# B250D.net
KiCad netlist of a schematic drawn in EAGLE
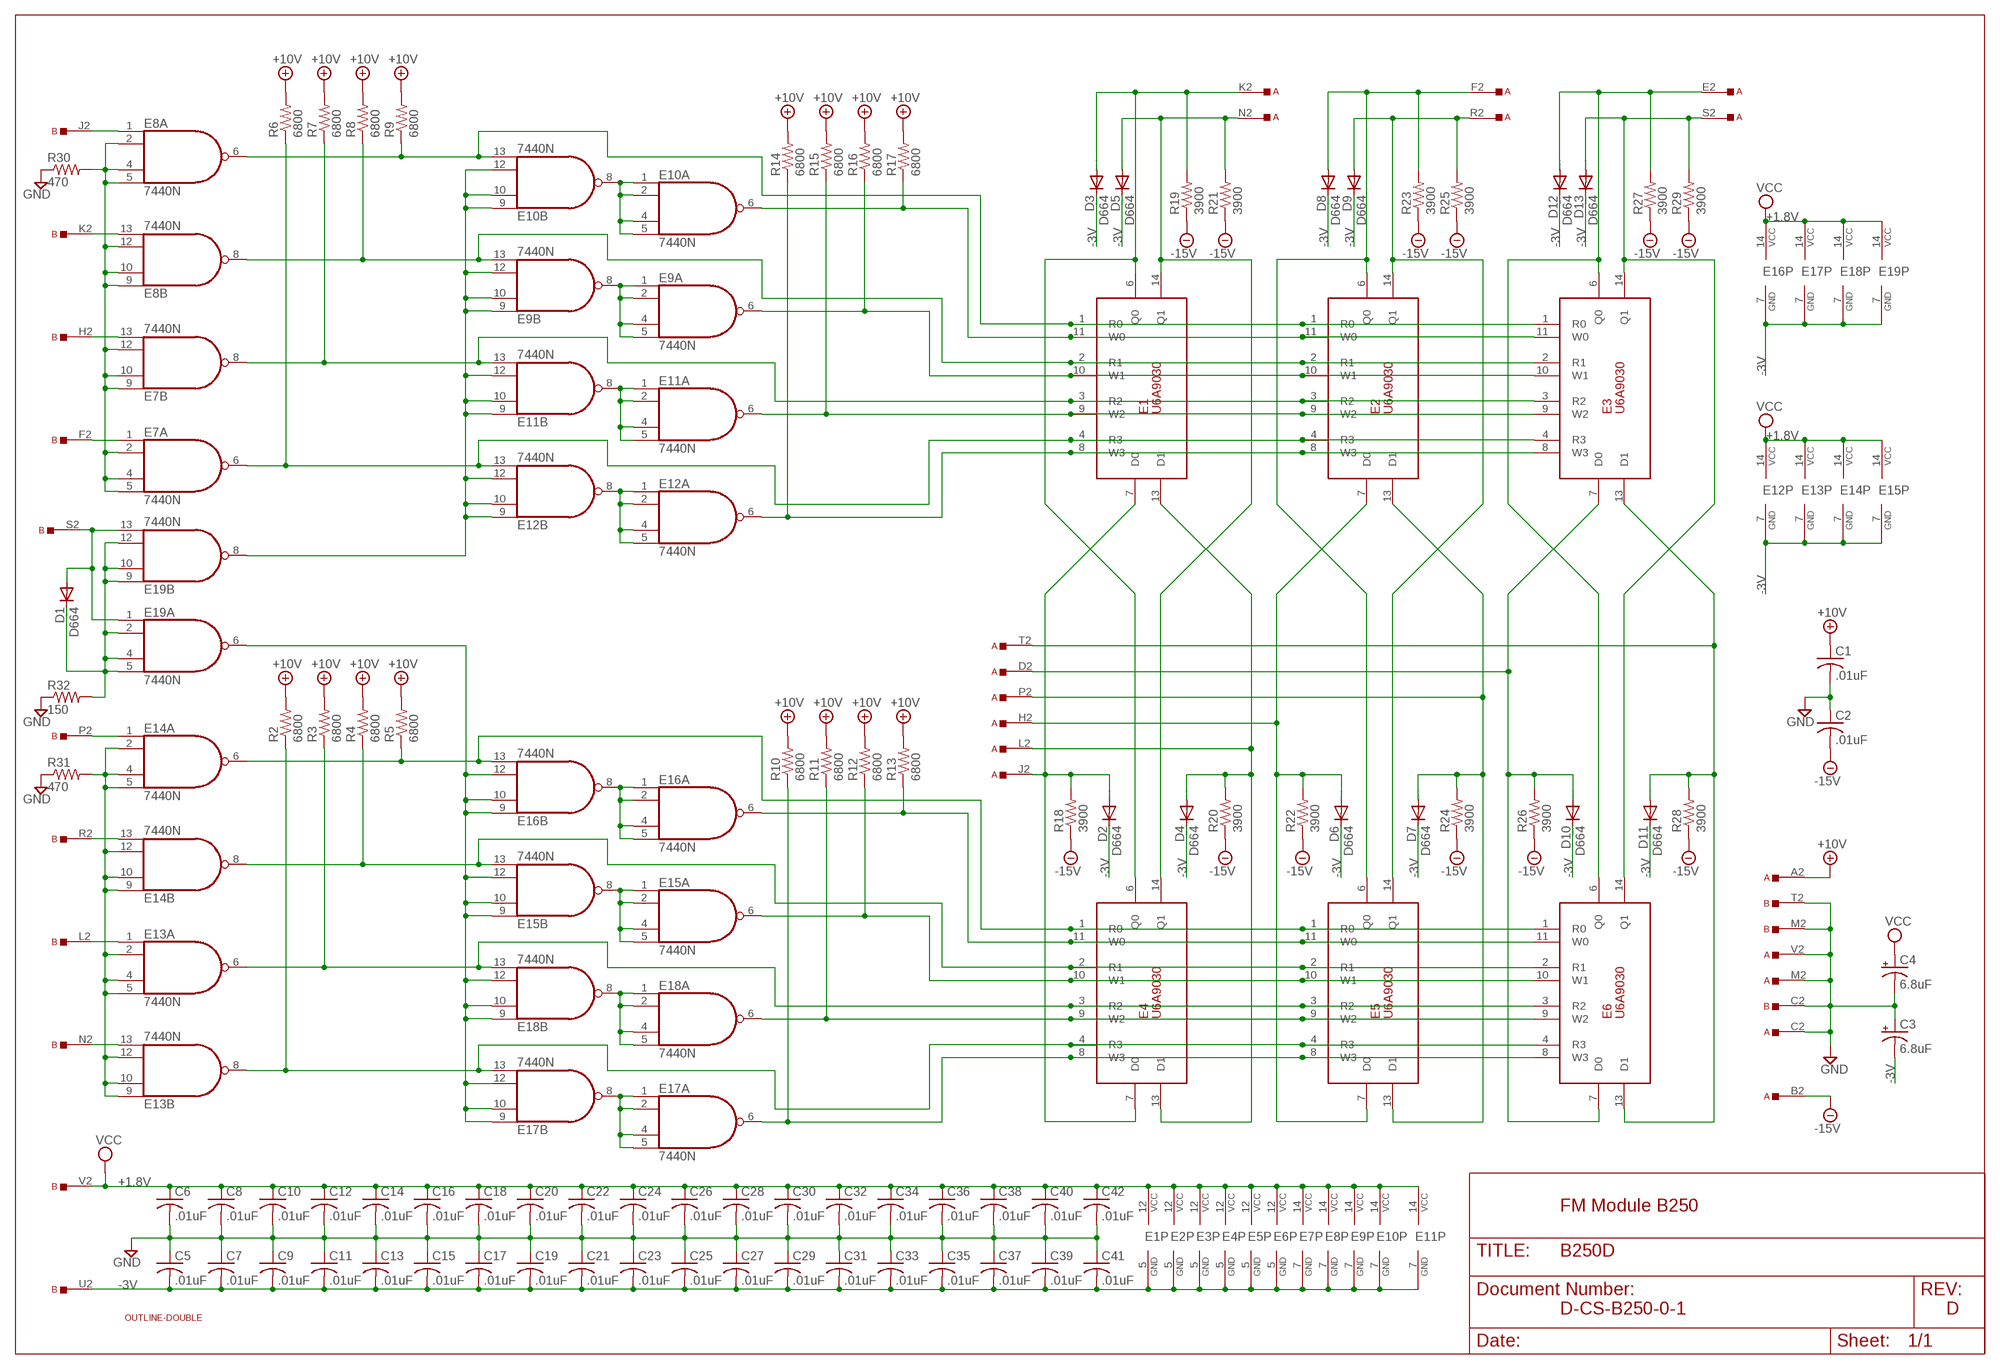
[diagram p0: schematic, sheet 1]

(export (version "E")
  (design (tool "Eeschema 10.0.6"))
  (components
    (comp (ref "A")
      (value "SS-TOP")
      (footprint "eagle-import:EDGE-CON1")
      (libsource (lib "eagle-import") (part "SS-TOP"))
    )
    (comp (ref "B")
      (value "SS-TOP")
      (footprint "eagle-import:EDGE-CON1")
      (libsource (lib "eagle-import") (part "SS-TOP"))
    )
    (comp (ref "C1")
      (value ".01uF")
      (footprint "eagle-import:C063-025X075")
      (libsource (lib "eagle-import") (part "C-US"))
    )
    (comp (ref "C2")
      (value ".01uF")
      (footprint "eagle-import:C063-025X075")
      (libsource (lib "eagle-import") (part "C-US"))
    )
    (comp (ref "C3")
      (value "6.8uF")
      (footprint "eagle-import:E15-5")
      (libsource (lib "eagle-import") (part "CPOL-USE15-5AXIAL"))
    )
    (comp (ref "C4")
      (value "6.8uF")
      (footprint "eagle-import:E15-5")
      (libsource (lib "eagle-import") (part "CPOL-USE15-5AXIAL"))
    )
    (comp (ref "C5")
      (value ".01uF")
      (footprint "eagle-import:C063-025X075")
      (libsource (lib "eagle-import") (part "C-US"))
    )
    (comp (ref "C6")
      (value ".01uF")
      (footprint "eagle-import:C063-025X075")
      (libsource (lib "eagle-import") (part "C-US"))
    )
    (comp (ref "C7")
      (value ".01uF")
      (footprint "eagle-import:C063-025X075")
      (libsource (lib "eagle-import") (part "C-US"))
    )
    (comp (ref "C8")
      (value ".01uF")
      (footprint "eagle-import:C063-025X075")
      (libsource (lib "eagle-import") (part "C-US"))
    )
    (comp (ref "C9")
      (value ".01uF")
      (footprint "eagle-import:C063-025X075")
      (libsource (lib "eagle-import") (part "C-US"))
    )
    (comp (ref "C10")
      (value ".01uF")
      (footprint "eagle-import:C063-025X075")
      (libsource (lib "eagle-import") (part "C-US"))
    )
    (comp (ref "C11")
      (value ".01uF")
      (footprint "eagle-import:C063-025X075")
      (libsource (lib "eagle-import") (part "C-US"))
    )
    (comp (ref "C12")
      (value ".01uF")
      (footprint "eagle-import:C063-025X075")
      (libsource (lib "eagle-import") (part "C-US"))
    )
    (comp (ref "C13")
      (value ".01uF")
      (footprint "eagle-import:C063-025X075")
      (libsource (lib "eagle-import") (part "C-US"))
    )
    (comp (ref "C14")
      (value ".01uF")
      (footprint "eagle-import:C063-025X075")
      (libsource (lib "eagle-import") (part "C-US"))
    )
    (comp (ref "C15")
      (value ".01uF")
      (footprint "eagle-import:C063-025X075")
      (libsource (lib "eagle-import") (part "C-US"))
    )
    (comp (ref "C16")
      (value ".01uF")
      (footprint "eagle-import:C063-025X075")
      (libsource (lib "eagle-import") (part "C-US"))
    )
    (comp (ref "C17")
      (value ".01uF")
      (footprint "eagle-import:C063-025X075")
      (libsource (lib "eagle-import") (part "C-US"))
    )
    (comp (ref "C18")
      (value ".01uF")
      (footprint "eagle-import:C063-025X075")
      (libsource (lib "eagle-import") (part "C-US"))
    )
    (comp (ref "C19")
      (value ".01uF")
      (footprint "eagle-import:C063-025X075")
      (libsource (lib "eagle-import") (part "C-US"))
    )
    (comp (ref "C20")
      (value ".01uF")
      (footprint "eagle-import:C063-025X075")
      (libsource (lib "eagle-import") (part "C-US"))
    )
    (comp (ref "C21")
      (value ".01uF")
      (footprint "eagle-import:C063-025X075")
      (libsource (lib "eagle-import") (part "C-US"))
    )
    (comp (ref "C22")
      (value ".01uF")
      (footprint "eagle-import:C063-025X075")
      (libsource (lib "eagle-import") (part "C-US"))
    )
    (comp (ref "C23")
      (value ".01uF")
      (footprint "eagle-import:C063-025X075")
      (libsource (lib "eagle-import") (part "C-US"))
    )
    (comp (ref "C24")
      (value ".01uF")
      (footprint "eagle-import:C063-025X075")
      (libsource (lib "eagle-import") (part "C-US"))
    )
    (comp (ref "C25")
      (value ".01uF")
      (footprint "eagle-import:C063-025X075")
      (libsource (lib "eagle-import") (part "C-US"))
    )
    (comp (ref "C26")
      (value ".01uF")
      (footprint "eagle-import:C063-025X075")
      (libsource (lib "eagle-import") (part "C-US"))
    )
    (comp (ref "C27")
      (value ".01uF")
      (footprint "eagle-import:C063-025X075")
      (libsource (lib "eagle-import") (part "C-US"))
    )
    (comp (ref "C28")
      (value ".01uF")
      (footprint "eagle-import:C063-025X075")
      (libsource (lib "eagle-import") (part "C-US"))
    )
    (comp (ref "C29")
      (value ".01uF")
      (footprint "eagle-import:C063-025X075")
      (libsource (lib "eagle-import") (part "C-US"))
    )
    (comp (ref "C30")
      (value ".01uF")
      (footprint "eagle-import:C063-025X075")
      (libsource (lib "eagle-import") (part "C-US"))
    )
    (comp (ref "C31")
      (value ".01uF")
      (footprint "eagle-import:C063-025X075")
      (libsource (lib "eagle-import") (part "C-US"))
    )
    (comp (ref "C32")
      (value ".01uF")
      (footprint "eagle-import:C063-025X075")
      (libsource (lib "eagle-import") (part "C-US"))
    )
    (comp (ref "C33")
      (value ".01uF")
      (footprint "eagle-import:C063-025X075")
      (libsource (lib "eagle-import") (part "C-US"))
    )
    (comp (ref "C34")
      (value ".01uF")
      (footprint "eagle-import:C063-025X075")
      (libsource (lib "eagle-import") (part "C-US"))
    )
    (comp (ref "C35")
      (value ".01uF")
      (footprint "eagle-import:C063-025X075")
      (libsource (lib "eagle-import") (part "C-US"))
    )
    (comp (ref "C36")
      (value ".01uF")
      (footprint "eagle-import:C063-025X075")
      (libsource (lib "eagle-import") (part "C-US"))
    )
    (comp (ref "C37")
      (value ".01uF")
      (footprint "eagle-import:C063-025X075")
      (libsource (lib "eagle-import") (part "C-US"))
    )
    (comp (ref "C38")
      (value ".01uF")
      (footprint "eagle-import:C063-025X075")
      (libsource (lib "eagle-import") (part "C-US"))
    )
    (comp (ref "C39")
      (value ".01uF")
      (footprint "eagle-import:C063-025X075")
      (libsource (lib "eagle-import") (part "C-US"))
    )
    (comp (ref "C40")
      (value ".01uF")
      (footprint "eagle-import:C063-025X075")
      (libsource (lib "eagle-import") (part "C-US"))
    )
    (comp (ref "C41")
      (value ".01uF")
      (footprint "eagle-import:C063-025X075")
      (libsource (lib "eagle-import") (part "C-US"))
    )
    (comp (ref "C42")
      (value ".01uF")
      (footprint "eagle-import:C063-025X075")
      (libsource (lib "eagle-import") (part "C-US"))
    )
    (comp (ref "D1")
      (value "D664")
      (footprint "eagle-import:DO35-10")
      (libsource (lib "eagle-import") (part "DIODE-DO35-10"))
    )
    (comp (ref "D2")
      (value "D664")
      (footprint "eagle-import:DO35-10")
      (libsource (lib "eagle-import") (part "DIODE-DO35-10"))
    )
    (comp (ref "D3")
      (value "D664")
      (footprint "eagle-import:DO35-10")
      (libsource (lib "eagle-import") (part "DIODE-DO35-10"))
    )
    (comp (ref "D4")
      (value "D664")
      (footprint "eagle-import:DO35-10")
      (libsource (lib "eagle-import") (part "DIODE-DO35-10"))
    )
    (comp (ref "D5")
      (value "D664")
      (footprint "eagle-import:DO35-10")
      (libsource (lib "eagle-import") (part "DIODE-DO35-10"))
    )
    (comp (ref "D6")
      (value "D664")
      (footprint "eagle-import:DO35-10")
      (libsource (lib "eagle-import") (part "DIODE-DO35-10"))
    )
    (comp (ref "D7")
      (value "D664")
      (footprint "eagle-import:DO35-10")
      (libsource (lib "eagle-import") (part "DIODE-DO35-10"))
    )
    (comp (ref "D8")
      (value "D664")
      (footprint "eagle-import:DO35-10")
      (libsource (lib "eagle-import") (part "DIODE-DO35-10"))
    )
    (comp (ref "D9")
      (value "D664")
      (footprint "eagle-import:DO35-10")
      (libsource (lib "eagle-import") (part "DIODE-DO35-10"))
    )
    (comp (ref "D10")
      (value "D664")
      (footprint "eagle-import:DO35-10")
      (libsource (lib "eagle-import") (part "DIODE-DO35-10"))
    )
    (comp (ref "D11")
      (value "D664")
      (footprint "eagle-import:DO35-10")
      (libsource (lib "eagle-import") (part "DIODE-DO35-10"))
    )
    (comp (ref "D12")
      (value "D664")
      (footprint "eagle-import:DO35-10")
      (libsource (lib "eagle-import") (part "DIODE-DO35-10"))
    )
    (comp (ref "D13")
      (value "D664")
      (footprint "eagle-import:DO35-10")
      (libsource (lib "eagle-import") (part "DIODE-DO35-10"))
    )
    (comp (ref "E1")
      (value "U6A9030")
      (footprint "eagle-import:DIL14")
      (libsource (lib "eagle-import") (part "U6A9030"))
    )
    (comp (ref "E2")
      (value "U6A9030")
      (footprint "eagle-import:DIL14")
      (libsource (lib "eagle-import") (part "U6A9030"))
    )
    (comp (ref "E3")
      (value "U6A9030")
      (footprint "eagle-import:DIL14")
      (libsource (lib "eagle-import") (part "U6A9030"))
    )
    (comp (ref "E4")
      (value "U6A9030")
      (footprint "eagle-import:DIL14")
      (libsource (lib "eagle-import") (part "U6A9030"))
    )
    (comp (ref "E5")
      (value "U6A9030")
      (footprint "eagle-import:DIL14")
      (libsource (lib "eagle-import") (part "U6A9030"))
    )
    (comp (ref "E6")
      (value "U6A9030")
      (footprint "eagle-import:DIL14")
      (libsource (lib "eagle-import") (part "U6A9030"))
    )
    (comp (ref "E7")
      (value "7440N")
      (footprint "eagle-import:DIL14")
      (libsource (lib "eagle-import") (part "7440N"))
    )
    (comp (ref "E8")
      (value "7440N")
      (footprint "eagle-import:DIL14")
      (libsource (lib "eagle-import") (part "7440N"))
    )
    (comp (ref "E9")
      (value "7440N")
      (footprint "eagle-import:DIL14")
      (libsource (lib "eagle-import") (part "7440N"))
    )
    (comp (ref "E10")
      (value "7440N")
      (footprint "eagle-import:DIL14")
      (libsource (lib "eagle-import") (part "7440N"))
    )
    (comp (ref "E11")
      (value "7440N")
      (footprint "eagle-import:DIL14")
      (libsource (lib "eagle-import") (part "7440N"))
    )
    (comp (ref "E12")
      (value "7440N")
      (footprint "eagle-import:DIL14")
      (libsource (lib "eagle-import") (part "7440N"))
    )
    (comp (ref "E13")
      (value "7440N")
      (footprint "eagle-import:DIL14")
      (libsource (lib "eagle-import") (part "7440N"))
    )
    (comp (ref "E14")
      (value "7440N")
      (footprint "eagle-import:DIL14")
      (libsource (lib "eagle-import") (part "7440N"))
    )
    (comp (ref "E15")
      (value "7440N")
      (footprint "eagle-import:DIL14")
      (libsource (lib "eagle-import") (part "7440N"))
    )
    (comp (ref "E16")
      (value "7440N")
      (footprint "eagle-import:DIL14")
      (libsource (lib "eagle-import") (part "7440N"))
    )
    (comp (ref "E17")
      (value "7440N")
      (footprint "eagle-import:DIL14")
      (libsource (lib "eagle-import") (part "7440N"))
    )
    (comp (ref "E18")
      (value "7440N")
      (footprint "eagle-import:DIL14")
      (libsource (lib "eagle-import") (part "7440N"))
    )
    (comp (ref "E19")
      (value "7440N")
      (footprint "eagle-import:DIL14")
      (libsource (lib "eagle-import") (part "7440N"))
    )
    (comp (ref "R2")
      (value "6800")
      (footprint "eagle-import:0207_10")
      (libsource (lib "eagle-import") (part "R-US_0207/10"))
    )
    (comp (ref "R3")
      (value "6800")
      (footprint "eagle-import:0207_10")
      (libsource (lib "eagle-import") (part "R-US_0207/10"))
    )
    (comp (ref "R4")
      (value "6800")
      (footprint "eagle-import:0207_10")
      (libsource (lib "eagle-import") (part "R-US_0207/10"))
    )
    (comp (ref "R5")
      (value "6800")
      (footprint "eagle-import:0207_10")
      (libsource (lib "eagle-import") (part "R-US_0207/10"))
    )
    (comp (ref "R6")
      (value "6800")
      (footprint "eagle-import:0207_10")
      (libsource (lib "eagle-import") (part "R-US_0207/10"))
    )
    (comp (ref "R7")
      (value "6800")
      (footprint "eagle-import:0207_10")
      (libsource (lib "eagle-import") (part "R-US_0207/10"))
    )
    (comp (ref "R8")
      (value "6800")
      (footprint "eagle-import:0207_10")
      (libsource (lib "eagle-import") (part "R-US_0207/10"))
    )
    (comp (ref "R9")
      (value "6800")
      (footprint "eagle-import:0207_10")
      (libsource (lib "eagle-import") (part "R-US_0207/10"))
    )
    (comp (ref "R10")
      (value "6800")
      (footprint "eagle-import:0207_10")
      (libsource (lib "eagle-import") (part "R-US_0207/10"))
    )
    (comp (ref "R11")
      (value "6800")
      (footprint "eagle-import:0207_10")
      (libsource (lib "eagle-import") (part "R-US_0207/10"))
    )
    (comp (ref "R12")
      (value "6800")
      (footprint "eagle-import:0207_10")
      (libsource (lib "eagle-import") (part "R-US_0207/10"))
    )
    (comp (ref "R13")
      (value "6800")
      (footprint "eagle-import:0207_10")
      (libsource (lib "eagle-import") (part "R-US_0207/10"))
    )
    (comp (ref "R14")
      (value "6800")
      (footprint "eagle-import:0207_10")
      (libsource (lib "eagle-import") (part "R-US_0207/10"))
    )
    (comp (ref "R15")
      (value "6800")
      (footprint "eagle-import:0207_10")
      (libsource (lib "eagle-import") (part "R-US_0207/10"))
    )
    (comp (ref "R16")
      (value "6800")
      (footprint "eagle-import:0207_10")
      (libsource (lib "eagle-import") (part "R-US_0207/10"))
    )
    (comp (ref "R17")
      (value "6800")
      (footprint "eagle-import:0207_10")
      (libsource (lib "eagle-import") (part "R-US_0207/10"))
    )
    (comp (ref "R18")
      (value "3900")
      (footprint "eagle-import:0207_10")
      (libsource (lib "eagle-import") (part "R-US_0207/10"))
    )
    (comp (ref "R19")
      (value "3900")
      (footprint "eagle-import:0207_10")
      (libsource (lib "eagle-import") (part "R-US_0207/10"))
    )
    (comp (ref "R20")
      (value "3900")
      (footprint "eagle-import:0207_10")
      (libsource (lib "eagle-import") (part "R-US_0207/10"))
    )
    (comp (ref "R21")
      (value "3900")
      (footprint "eagle-import:0207_10")
      (libsource (lib "eagle-import") (part "R-US_0207/10"))
    )
    (comp (ref "R22")
      (value "3900")
      (footprint "eagle-import:0207_10")
      (libsource (lib "eagle-import") (part "R-US_0207/10"))
    )
    (comp (ref "R23")
      (value "3900")
      (footprint "eagle-import:0207_10")
      (libsource (lib "eagle-import") (part "R-US_0207/10"))
    )
    (comp (ref "R24")
      (value "3900")
      (footprint "eagle-import:0207_10")
      (libsource (lib "eagle-import") (part "R-US_0207/10"))
    )
    (comp (ref "R25")
      (value "3900")
      (footprint "eagle-import:0207_10")
      (libsource (lib "eagle-import") (part "R-US_0207/10"))
    )
    (comp (ref "R26")
      (value "3900")
      (footprint "eagle-import:0207_10")
      (libsource (lib "eagle-import") (part "R-US_0207/10"))
    )
    (comp (ref "R27")
      (value "3900")
      (footprint "eagle-import:0207_10")
      (libsource (lib "eagle-import") (part "R-US_0207/10"))
    )
    (comp (ref "R28")
      (value "3900")
      (footprint "eagle-import:0207_10")
      (libsource (lib "eagle-import") (part "R-US_0207/10"))
    )
    (comp (ref "R29")
      (value "3900")
      (footprint "eagle-import:0207_10")
      (libsource (lib "eagle-import") (part "R-US_0207/10"))
    )
    (comp (ref "R30")
      (value "470")
      (footprint "eagle-import:0207_10")
      (libsource (lib "eagle-import") (part "R-US_0207/10"))
    )
    (comp (ref "R31")
      (value "470")
      (footprint "eagle-import:0207_10")
      (libsource (lib "eagle-import") (part "R-US_0207/10"))
    )
    (comp (ref "R32")
      (value "150")
      (footprint "eagle-import:0207_10")
      (libsource (lib "eagle-import") (part "R-US_0207/10"))
    )
    (comp (ref "U$1")
      (value "OUTLINE-DOUBLE")
      (footprint "eagle-import:DOUBLE")
      (libsource (lib "eagle-import") (part "OUTLINE-DOUBLE"))
    )
  )
  (nets
    (net (code "1") (name "+10V") (class "Default")
      (node (ref "A") (pin "A2") (pinfunction "P_A2") (pintype "passive"))
      (node (ref "C1") (pin "1") (pinfunction "1_1") (pintype "passive"))
      (node (ref "R10") (pin "2") (pinfunction "2_2") (pintype "passive"))
      (node (ref "R11") (pin "2") (pinfunction "2_2") (pintype "passive"))
      (node (ref "R12") (pin "2") (pinfunction "2_2") (pintype "passive"))
      (node (ref "R13") (pin "2") (pinfunction "2_2") (pintype "passive"))
      (node (ref "R14") (pin "2") (pinfunction "2_2") (pintype "passive"))
      (node (ref "R15") (pin "2") (pinfunction "2_2") (pintype "passive"))
      (node (ref "R16") (pin "2") (pinfunction "2_2") (pintype "passive"))
      (node (ref "R17") (pin "2") (pinfunction "2_2") (pintype "passive"))
      (node (ref "R2") (pin "2") (pinfunction "2_2") (pintype "passive"))
      (node (ref "R3") (pin "2") (pinfunction "2_2") (pintype "passive"))
      (node (ref "R4") (pin "2") (pinfunction "2_2") (pintype "passive"))
      (node (ref "R5") (pin "2") (pinfunction "2_2") (pintype "passive"))
      (node (ref "R6") (pin "2") (pinfunction "2_2") (pintype "passive"))
      (node (ref "R7") (pin "2") (pinfunction "2_2") (pintype "passive"))
      (node (ref "R8") (pin "2") (pinfunction "2_2") (pintype "passive"))
      (node (ref "R9") (pin "2") (pinfunction "2_2") (pintype "passive"))
    )
    (net (code "2") (name "-15V") (class "Default")
      (node (ref "A") (pin "B2") (pinfunction "P_B2") (pintype "passive"))
      (node (ref "C2") (pin "2") (pinfunction "2_2") (pintype "passive"))
      (node (ref "R18") (pin "1") (pinfunction "1_1") (pintype "passive"))
      (node (ref "R19") (pin "1") (pinfunction "1_1") (pintype "passive"))
      (node (ref "R20") (pin "1") (pinfunction "1_1") (pintype "passive"))
      (node (ref "R21") (pin "1") (pinfunction "1_1") (pintype "passive"))
      (node (ref "R22") (pin "1") (pinfunction "1_1") (pintype "passive"))
      (node (ref "R23") (pin "1") (pinfunction "1_1") (pintype "passive"))
      (node (ref "R24") (pin "1") (pinfunction "1_1") (pintype "passive"))
      (node (ref "R25") (pin "1") (pinfunction "1_1") (pintype "passive"))
      (node (ref "R26") (pin "1") (pinfunction "1_1") (pintype "passive"))
      (node (ref "R27") (pin "1") (pinfunction "1_1") (pintype "passive"))
      (node (ref "R28") (pin "1") (pinfunction "1_1") (pintype "passive"))
      (node (ref "R29") (pin "1") (pinfunction "1_1") (pintype "passive"))
    )
    (net (code "3") (name "/-3V") (class "Default")
      (node (ref "B") (pin "U2") (pinfunction "P_U2") (pintype "passive"))
      (node (ref "C11") (pin "2") (pinfunction "2_2") (pintype "passive"))
      (node (ref "C13") (pin "2") (pinfunction "2_2") (pintype "passive"))
      (node (ref "C15") (pin "2") (pinfunction "2_2") (pintype "passive"))
      (node (ref "C17") (pin "2") (pinfunction "2_2") (pintype "passive"))
      (node (ref "C19") (pin "2") (pinfunction "2_2") (pintype "passive"))
      (node (ref "C21") (pin "2") (pinfunction "2_2") (pintype "passive"))
      (node (ref "C23") (pin "2") (pinfunction "2_2") (pintype "passive"))
      (node (ref "C25") (pin "2") (pinfunction "2_2") (pintype "passive"))
      (node (ref "C27") (pin "2") (pinfunction "2_2") (pintype "passive"))
      (node (ref "C29") (pin "2") (pinfunction "2_2") (pintype "passive"))
      (node (ref "C3") (pin "-") (pinfunction "-_-") (pintype "passive"))
      (node (ref "C31") (pin "2") (pinfunction "2_2") (pintype "passive"))
      (node (ref "C33") (pin "2") (pinfunction "2_2") (pintype "passive"))
      (node (ref "C35") (pin "2") (pinfunction "2_2") (pintype "passive"))
      (node (ref "C37") (pin "2") (pinfunction "2_2") (pintype "passive"))
      (node (ref "C39") (pin "2") (pinfunction "2_2") (pintype "passive"))
      (node (ref "C41") (pin "2") (pinfunction "2_2") (pintype "passive"))
      (node (ref "C5") (pin "2") (pinfunction "2_2") (pintype "passive"))
      (node (ref "C7") (pin "2") (pinfunction "2_2") (pintype "passive"))
      (node (ref "C9") (pin "2") (pinfunction "2_2") (pintype "passive"))
      (node (ref "D10") (pin "C") (pinfunction "C_C") (pintype "passive"))
      (node (ref "D11") (pin "C") (pinfunction "C_C") (pintype "passive"))
      (node (ref "D12") (pin "C") (pinfunction "C_C") (pintype "passive"))
      (node (ref "D13") (pin "C") (pinfunction "C_C") (pintype "passive"))
      (node (ref "D2") (pin "C") (pinfunction "C_C") (pintype "passive"))
      (node (ref "D3") (pin "C") (pinfunction "C_C") (pintype "passive"))
      (node (ref "D4") (pin "C") (pinfunction "C_C") (pintype "passive"))
      (node (ref "D5") (pin "C") (pinfunction "C_C") (pintype "passive"))
      (node (ref "D6") (pin "C") (pinfunction "C_C") (pintype "passive"))
      (node (ref "D7") (pin "C") (pinfunction "C_C") (pintype "passive"))
      (node (ref "D8") (pin "C") (pinfunction "C_C") (pintype "passive"))
      (node (ref "D9") (pin "C") (pinfunction "C_C") (pintype "passive"))
      (node (ref "E1") (pin "5") (pinfunction "GND_5") (pintype "power_in"))
      (node (ref "E10") (pin "7") (pinfunction "GND_7") (pintype "power_in"))
      (node (ref "E11") (pin "7") (pinfunction "GND_7") (pintype "power_in"))
      (node (ref "E12") (pin "7") (pinfunction "GND_7") (pintype "power_in"))
      (node (ref "E13") (pin "7") (pinfunction "GND_7") (pintype "power_in"))
      (node (ref "E14") (pin "7") (pinfunction "GND_7") (pintype "power_in"))
      (node (ref "E15") (pin "7") (pinfunction "GND_7") (pintype "power_in"))
      (node (ref "E16") (pin "7") (pinfunction "GND_7") (pintype "power_in"))
      (node (ref "E17") (pin "7") (pinfunction "GND_7") (pintype "power_in"))
      (node (ref "E18") (pin "7") (pinfunction "GND_7") (pintype "power_in"))
      (node (ref "E19") (pin "7") (pinfunction "GND_7") (pintype "power_in"))
      (node (ref "E2") (pin "5") (pinfunction "GND_5") (pintype "power_in"))
      (node (ref "E3") (pin "5") (pinfunction "GND_5") (pintype "power_in"))
      (node (ref "E4") (pin "5") (pinfunction "GND_5") (pintype "power_in"))
      (node (ref "E5") (pin "5") (pinfunction "GND_5") (pintype "power_in"))
      (node (ref "E6") (pin "5") (pinfunction "GND_5") (pintype "power_in"))
      (node (ref "E7") (pin "7") (pinfunction "GND_7") (pintype "power_in"))
      (node (ref "E8") (pin "7") (pinfunction "GND_7") (pintype "power_in"))
      (node (ref "E9") (pin "7") (pinfunction "GND_7") (pintype "power_in"))
    )
    (net (code "4") (name "GND") (class "Default")
      (node (ref "A") (pin "C2") (pinfunction "P_C2") (pintype "passive"))
      (node (ref "A") (pin "M2") (pinfunction "P_M2") (pintype "passive"))
      (node (ref "A") (pin "V2") (pinfunction "P_V2") (pintype "passive"))
      (node (ref "B") (pin "C2") (pinfunction "P_C2") (pintype "passive"))
      (node (ref "B") (pin "M2") (pinfunction "P_M2") (pintype "passive"))
      (node (ref "B") (pin "T2") (pinfunction "P_T2") (pintype "passive"))
      (node (ref "C1") (pin "2") (pinfunction "2_2") (pintype "passive"))
      (node (ref "C10") (pin "2") (pinfunction "2_2") (pintype "passive"))
      (node (ref "C11") (pin "1") (pinfunction "1_1") (pintype "passive"))
      (node (ref "C12") (pin "2") (pinfunction "2_2") (pintype "passive"))
      (node (ref "C13") (pin "1") (pinfunction "1_1") (pintype "passive"))
      (node (ref "C14") (pin "2") (pinfunction "2_2") (pintype "passive"))
      (node (ref "C15") (pin "1") (pinfunction "1_1") (pintype "passive"))
      (node (ref "C16") (pin "2") (pinfunction "2_2") (pintype "passive"))
      (node (ref "C17") (pin "1") (pinfunction "1_1") (pintype "passive"))
      (node (ref "C18") (pin "2") (pinfunction "2_2") (pintype "passive"))
      (node (ref "C19") (pin "1") (pinfunction "1_1") (pintype "passive"))
      (node (ref "C2") (pin "1") (pinfunction "1_1") (pintype "passive"))
      (node (ref "C20") (pin "2") (pinfunction "2_2") (pintype "passive"))
      (node (ref "C21") (pin "1") (pinfunction "1_1") (pintype "passive"))
      (node (ref "C22") (pin "2") (pinfunction "2_2") (pintype "passive"))
      (node (ref "C23") (pin "1") (pinfunction "1_1") (pintype "passive"))
      (node (ref "C24") (pin "2") (pinfunction "2_2") (pintype "passive"))
      (node (ref "C25") (pin "1") (pinfunction "1_1") (pintype "passive"))
      (node (ref "C26") (pin "2") (pinfunction "2_2") (pintype "passive"))
      (node (ref "C27") (pin "1") (pinfunction "1_1") (pintype "passive"))
      (node (ref "C28") (pin "2") (pinfunction "2_2") (pintype "passive"))
      (node (ref "C29") (pin "1") (pinfunction "1_1") (pintype "passive"))
      (node (ref "C3") (pin "+") (pinfunction "+_+") (pintype "passive"))
      (node (ref "C30") (pin "2") (pinfunction "2_2") (pintype "passive"))
      (node (ref "C31") (pin "1") (pinfunction "1_1") (pintype "passive"))
      (node (ref "C32") (pin "2") (pinfunction "2_2") (pintype "passive"))
      (node (ref "C33") (pin "1") (pinfunction "1_1") (pintype "passive"))
      (node (ref "C34") (pin "2") (pinfunction "2_2") (pintype "passive"))
      (node (ref "C35") (pin "1") (pinfunction "1_1") (pintype "passive"))
      (node (ref "C36") (pin "2") (pinfunction "2_2") (pintype "passive"))
      (node (ref "C37") (pin "1") (pinfunction "1_1") (pintype "passive"))
      (node (ref "C38") (pin "2") (pinfunction "2_2") (pintype "passive"))
      (node (ref "C39") (pin "1") (pinfunction "1_1") (pintype "passive"))
      (node (ref "C4") (pin "-") (pinfunction "-_-") (pintype "passive"))
      (node (ref "C40") (pin "2") (pinfunction "2_2") (pintype "passive"))
      (node (ref "C41") (pin "1") (pinfunction "1_1") (pintype "passive"))
      (node (ref "C42") (pin "2") (pinfunction "2_2") (pintype "passive"))
      (node (ref "C5") (pin "1") (pinfunction "1_1") (pintype "passive"))
      (node (ref "C6") (pin "2") (pinfunction "2_2") (pintype "passive"))
      (node (ref "C7") (pin "1") (pinfunction "1_1") (pintype "passive"))
      (node (ref "C8") (pin "2") (pinfunction "2_2") (pintype "passive"))
      (node (ref "C9") (pin "1") (pinfunction "1_1") (pintype "passive"))
      (node (ref "R30") (pin "1") (pinfunction "1_1") (pintype "passive"))
      (node (ref "R31") (pin "1") (pinfunction "1_1") (pintype "passive"))
      (node (ref "R32") (pin "1") (pinfunction "1_1") (pintype "passive"))
    )
    (net (code "5") (name "Net-(AD-P)") (class "Default")
      (node (ref "A") (pin "D2") (pinfunction "P_D2") (pintype "passive"))
      (node (ref "D10") (pin "A") (pinfunction "A_A") (pintype "passive"))
      (node (ref "E3") (pin "7") (pinfunction "D0_7") (pintype "input"))
      (node (ref "E6") (pin "7") (pinfunction "D0_7") (pintype "input"))
      (node (ref "R26") (pin "2") (pinfunction "2_2") (pintype "passive"))
    )
    (net (code "6") (name "Net-(AE-P)") (class "Default")
      (node (ref "A") (pin "E2") (pinfunction "P_E2") (pintype "passive"))
      (node (ref "D12") (pin "A") (pinfunction "A_A") (pintype "passive"))
      (node (ref "E3") (pin "6") (pinfunction "Q0_6") (pintype "open_collector"))
      (node (ref "E6") (pin "6") (pinfunction "Q0_6") (pintype "open_collector"))
      (node (ref "R27") (pin "2") (pinfunction "2_2") (pintype "passive"))
    )
    (net (code "7") (name "Net-(AF-P)") (class "Default")
      (node (ref "A") (pin "F2") (pinfunction "P_F2") (pintype "passive"))
      (node (ref "D8") (pin "A") (pinfunction "A_A") (pintype "passive"))
      (node (ref "E2") (pin "6") (pinfunction "Q0_6") (pintype "open_collector"))
      (node (ref "E5") (pin "6") (pinfunction "Q0_6") (pintype "open_collector"))
      (node (ref "R23") (pin "2") (pinfunction "2_2") (pintype "passive"))
    )
    (net (code "8") (name "Net-(AG-P)") (class "Default")
      (node (ref "A") (pin "H2") (pinfunction "P_H2") (pintype "passive"))
      (node (ref "D6") (pin "A") (pinfunction "A_A") (pintype "passive"))
      (node (ref "E2") (pin "7") (pinfunction "D0_7") (pintype "input"))
      (node (ref "E5") (pin "7") (pinfunction "D0_7") (pintype "input"))
      (node (ref "R22") (pin "2") (pinfunction "2_2") (pintype "passive"))
    )
    (net (code "9") (name "Net-(AH-P)") (class "Default")
      (node (ref "A") (pin "J2") (pinfunction "P_J2") (pintype "passive"))
      (node (ref "D2") (pin "A") (pinfunction "A_A") (pintype "passive"))
      (node (ref "E1") (pin "7") (pinfunction "D0_7") (pintype "input"))
      (node (ref "E4") (pin "7") (pinfunction "D0_7") (pintype "input"))
      (node (ref "R18") (pin "2") (pinfunction "2_2") (pintype "passive"))
    )
    (net (code "10") (name "Net-(AI-P)") (class "Default")
      (node (ref "A") (pin "K2") (pinfunction "P_K2") (pintype "passive"))
      (node (ref "D3") (pin "A") (pinfunction "A_A") (pintype "passive"))
      (node (ref "E1") (pin "6") (pinfunction "Q0_6") (pintype "open_collector"))
      (node (ref "E4") (pin "6") (pinfunction "Q0_6") (pintype "open_collector"))
      (node (ref "R19") (pin "2") (pinfunction "2_2") (pintype "passive"))
    )
    (net (code "11") (name "Net-(AJ-P)") (class "Default")
      (node (ref "A") (pin "L2") (pinfunction "P_L2") (pintype "passive"))
      (node (ref "D4") (pin "A") (pinfunction "A_A") (pintype "passive"))
      (node (ref "E1") (pin "13") (pinfunction "D1_13") (pintype "input"))
      (node (ref "E4") (pin "13") (pinfunction "D1_13") (pintype "input"))
      (node (ref "R20") (pin "2") (pinfunction "2_2") (pintype "passive"))
    )
    (net (code "12") (name "Net-(AL-P)") (class "Default")
      (node (ref "A") (pin "N2") (pinfunction "P_N2") (pintype "passive"))
      (node (ref "D5") (pin "A") (pinfunction "A_A") (pintype "passive"))
      (node (ref "E1") (pin "14") (pinfunction "Q1_14") (pintype "open_collector"))
      (node (ref "E4") (pin "14") (pinfunction "Q1_14") (pintype "open_collector"))
      (node (ref "R21") (pin "2") (pinfunction "2_2") (pintype "passive"))
    )
    (net (code "13") (name "Net-(AM-P)") (class "Default")
      (node (ref "A") (pin "P2") (pinfunction "P_P2") (pintype "passive"))
      (node (ref "D7") (pin "A") (pinfunction "A_A") (pintype "passive"))
      (node (ref "E2") (pin "13") (pinfunction "D1_13") (pintype "input"))
      (node (ref "E5") (pin "13") (pinfunction "D1_13") (pintype "input"))
      (node (ref "R24") (pin "2") (pinfunction "2_2") (pintype "passive"))
    )
    (net (code "14") (name "Net-(AN-P)") (class "Default")
      (node (ref "A") (pin "R2") (pinfunction "P_R2") (pintype "passive"))
      (node (ref "D9") (pin "A") (pinfunction "A_A") (pintype "passive"))
      (node (ref "E2") (pin "14") (pinfunction "Q1_14") (pintype "open_collector"))
      (node (ref "E5") (pin "14") (pinfunction "Q1_14") (pintype "open_collector"))
      (node (ref "R25") (pin "2") (pinfunction "2_2") (pintype "passive"))
    )
    (net (code "15") (name "Net-(AO-P)") (class "Default")
      (node (ref "A") (pin "S2") (pinfunction "P_S2") (pintype "passive"))
      (node (ref "D13") (pin "A") (pinfunction "A_A") (pintype "passive"))
      (node (ref "E3") (pin "14") (pinfunction "Q1_14") (pintype "open_collector"))
      (node (ref "E6") (pin "14") (pinfunction "Q1_14") (pintype "open_collector"))
      (node (ref "R29") (pin "2") (pinfunction "2_2") (pintype "passive"))
    )
    (net (code "16") (name "Net-(AP-P)") (class "Default")
      (node (ref "A") (pin "T2") (pinfunction "P_T2") (pintype "passive"))
      (node (ref "D11") (pin "A") (pinfunction "A_A") (pintype "passive"))
      (node (ref "E3") (pin "13") (pinfunction "D1_13") (pintype "input"))
      (node (ref "E6") (pin "13") (pinfunction "D1_13") (pintype "input"))
      (node (ref "R28") (pin "2") (pinfunction "2_2") (pintype "passive"))
    )
    (net (code "17") (name "Net-(BF-P)") (class "Default")
      (node (ref "B") (pin "F2") (pinfunction "P_F2") (pintype "passive"))
      (node (ref "E7") (pin "1") (pinfunction "I0_1") (pintype "input"))
    )
    (net (code "18") (name "Net-(BG-P)") (class "Default")
      (node (ref "B") (pin "H2") (pinfunction "P_H2") (pintype "passive"))
      (node (ref "E7") (pin "13") (pinfunction "I3_13") (pintype "input"))
    )
    (net (code "19") (name "Net-(BH-P)") (class "Default")
      (node (ref "B") (pin "J2") (pinfunction "P_J2") (pintype "passive"))
      (node (ref "E8") (pin "1") (pinfunction "I0_1") (pintype "input"))
    )
    (net (code "20") (name "Net-(BI-P)") (class "Default")
      (node (ref "B") (pin "K2") (pinfunction "P_K2") (pintype "passive"))
      (node (ref "E8") (pin "13") (pinfunction "I3_13") (pintype "input"))
    )
    (net (code "21") (name "Net-(BJ-P)") (class "Default")
      (node (ref "B") (pin "L2") (pinfunction "P_L2") (pintype "passive"))
      (node (ref "E13") (pin "1") (pinfunction "I0_1") (pintype "input"))
    )
    (net (code "22") (name "Net-(BL-P)") (class "Default")
      (node (ref "B") (pin "N2") (pinfunction "P_N2") (pintype "passive"))
      (node (ref "E13") (pin "13") (pinfunction "I3_13") (pintype "input"))
    )
    (net (code "23") (name "Net-(BM-P)") (class "Default")
      (node (ref "B") (pin "P2") (pinfunction "P_P2") (pintype "passive"))
      (node (ref "E14") (pin "1") (pinfunction "I0_1") (pintype "input"))
    )
    (net (code "24") (name "Net-(BN-P)") (class "Default")
      (node (ref "B") (pin "R2") (pinfunction "P_R2") (pintype "passive"))
      (node (ref "E14") (pin "13") (pinfunction "I3_13") (pintype "input"))
    )
    (net (code "25") (name "Net-(BO-P)") (class "Default")
      (node (ref "B") (pin "S2") (pinfunction "P_S2") (pintype "passive"))
      (node (ref "D1") (pin "A") (pinfunction "A_A") (pintype "passive"))
      (node (ref "E19") (pin "1") (pinfunction "I0_1") (pintype "input"))
      (node (ref "E19") (pin "13") (pinfunction "I3_13") (pintype "input"))
    )
    (net (code "26") (name "Net-(E1A-R1)") (class "Default")
      (node (ref "E1") (pin "2") (pinfunction "R1_2") (pintype "input"))
      (node (ref "E2") (pin "2") (pinfunction "R1_2") (pintype "input"))
      (node (ref "E3") (pin "2") (pinfunction "R1_2") (pintype "input"))
      (node (ref "E8") (pin "8") (pinfunction "O_8") (pintype "output"))
      (node (ref "E9") (pin "13") (pinfunction "I3_13") (pintype "input"))
      (node (ref "R8") (pin "1") (pinfunction "1_1") (pintype "passive"))
    )
    (net (code "27") (name "Net-(E1A-W1)") (class "Default")
      (node (ref "E1") (pin "10") (pinfunction "W1_10") (pintype "input"))
      (node (ref "E2") (pin "10") (pinfunction "W1_10") (pintype "input"))
      (node (ref "E3") (pin "10") (pinfunction "W1_10") (pintype "input"))
      (node (ref "E9") (pin "6") (pinfunction "O_6") (pintype "output"))
      (node (ref "R16") (pin "1") (pinfunction "1_1") (pintype "passive"))
    )
    (net (code "28") (name "Net-(E7C-I1)") (class "Default")
      (node (ref "E7") (pin "10") (pinfunction "I1_10") (pintype "input"))
      (node (ref "E7") (pin "12") (pinfunction "I2_12") (pintype "input"))
      (node (ref "E7") (pin "2") (pinfunction "I1_2") (pintype "input"))
      (node (ref "E7") (pin "4") (pinfunction "I2_4") (pintype "input"))
      (node (ref "E7") (pin "5") (pinfunction "I3_5") (pintype "input"))
      (node (ref "E7") (pin "9") (pinfunction "I0_9") (pintype "input"))
      (node (ref "E8") (pin "10") (pinfunction "I1_10") (pintype "input"))
      (node (ref "E8") (pin "12") (pinfunction "I2_12") (pintype "input"))
      (node (ref "E8") (pin "2") (pinfunction "I1_2") (pintype "input"))
      (node (ref "E8") (pin "4") (pinfunction "I2_4") (pintype "input"))
      (node (ref "E8") (pin "5") (pinfunction "I3_5") (pintype "input"))
      (node (ref "E8") (pin "9") (pinfunction "I0_9") (pintype "input"))
      (node (ref "R30") (pin "2") (pinfunction "2_2") (pintype "passive"))
    )
    (net (code "29") (name "Net-(E9C-I0)") (class "Default")
      (node (ref "E9") (pin "1") (pinfunction "I0_1") (pintype "input"))
      (node (ref "E9") (pin "2") (pinfunction "I1_2") (pintype "input"))
      (node (ref "E9") (pin "4") (pinfunction "I2_4") (pintype "input"))
      (node (ref "E9") (pin "5") (pinfunction "I3_5") (pintype "input"))
      (node (ref "E9") (pin "8") (pinfunction "O_8") (pintype "output"))
    )
    (net (code "30") (name "Net-(E10C-I0)") (class "Default")
      (node (ref "E10") (pin "1") (pinfunction "I0_1") (pintype "input"))
      (node (ref "E10") (pin "2") (pinfunction "I1_2") (pintype "input"))
      (node (ref "E10") (pin "4") (pinfunction "I2_4") (pintype "input"))
      (node (ref "E10") (pin "5") (pinfunction "I3_5") (pintype "input"))
      (node (ref "E10") (pin "8") (pinfunction "O_8") (pintype "output"))
    )
    (net (code "31") (name "Net-(E10C-O)") (class "Default")
      (node (ref "E1") (pin "11") (pinfunction "W0_11") (pintype "input"))
      (node (ref "E10") (pin "6") (pinfunction "O_6") (pintype "output"))
      (node (ref "E2") (pin "11") (pinfunction "W0_11") (pintype "input"))
      (node (ref "E3") (pin "11") (pinfunction "W0_11") (pintype "input"))
      (node (ref "R17") (pin "1") (pinfunction "1_1") (pintype "passive"))
    )
    (net (code "32") (name "Net-(E10D-I0)") (class "Default")
      (node (ref "E10") (pin "10") (pinfunction "I1_10") (pintype "input"))
      (node (ref "E10") (pin "12") (pinfunction "I2_12") (pintype "input"))
      (node (ref "E10") (pin "9") (pinfunction "I0_9") (pintype "input"))
      (node (ref "E11") (pin "10") (pinfunction "I1_10") (pintype "input"))
      (node (ref "E11") (pin "12") (pinfunction "I2_12") (pintype "input"))
      (node (ref "E11") (pin "9") (pinfunction "I0_9") (pintype "input"))
      (node (ref "E12") (pin "10") (pinfunction "I1_10") (pintype "input"))
      (node (ref "E12") (pin "12") (pinfunction "I2_12") (pintype "input"))
      (node (ref "E12") (pin "9") (pinfunction "I0_9") (pintype "input"))
      (node (ref "E19") (pin "8") (pinfunction "O_8") (pintype "output"))
      (node (ref "E9") (pin "10") (pinfunction "I1_10") (pintype "input"))
      (node (ref "E9") (pin "12") (pinfunction "I2_12") (pintype "input"))
      (node (ref "E9") (pin "9") (pinfunction "I0_9") (pintype "input"))
    )
    (net (code "33") (name "Net-(E10D-I3)") (class "Default")
      (node (ref "E1") (pin "1") (pinfunction "R0_1") (pintype "input"))
      (node (ref "E10") (pin "13") (pinfunction "I3_13") (pintype "input"))
      (node (ref "E2") (pin "1") (pinfunction "R0_1") (pintype "input"))
      (node (ref "E3") (pin "1") (pinfunction "R0_1") (pintype "input"))
      (node (ref "E8") (pin "6") (pinfunction "O_6") (pintype "output"))
      (node (ref "R9") (pin "1") (pinfunction "1_1") (pintype "passive"))
    )
    (net (code "34") (name "Net-(E11C-I0)") (class "Default")
      (node (ref "E11") (pin "1") (pinfunction "I0_1") (pintype "input"))
      (node (ref "E11") (pin "2") (pinfunction "I1_2") (pintype "input"))
      (node (ref "E11") (pin "4") (pinfunction "I2_4") (pintype "input"))
      (node (ref "E11") (pin "5") (pinfunction "I3_5") (pintype "input"))
      (node (ref "E11") (pin "8") (pinfunction "O_8") (pintype "output"))
    )
    (net (code "35") (name "Net-(E11C-O)") (class "Default")
      (node (ref "E1") (pin "9") (pinfunction "W2_9") (pintype "input"))
      (node (ref "E11") (pin "6") (pinfunction "O_6") (pintype "output"))
      (node (ref "E2") (pin "9") (pinfunction "W2_9") (pintype "input"))
      (node (ref "E3") (pin "9") (pinfunction "W2_9") (pintype "input"))
      (node (ref "R15") (pin "1") (pinfunction "1_1") (pintype "passive"))
    )
    (net (code "36") (name "Net-(E11D-I3)") (class "Default")
      (node (ref "E1") (pin "3") (pinfunction "R2_3") (pintype "input"))
      (node (ref "E11") (pin "13") (pinfunction "I3_13") (pintype "input"))
      (node (ref "E2") (pin "3") (pinfunction "R2_3") (pintype "input"))
      (node (ref "E3") (pin "3") (pinfunction "R2_3") (pintype "input"))
      (node (ref "E7") (pin "8") (pinfunction "O_8") (pintype "output"))
      (node (ref "R7") (pin "1") (pinfunction "1_1") (pintype "passive"))
    )
    (net (code "37") (name "Net-(E12C-I0)") (class "Default")
      (node (ref "E12") (pin "1") (pinfunction "I0_1") (pintype "input"))
      (node (ref "E12") (pin "2") (pinfunction "I1_2") (pintype "input"))
      (node (ref "E12") (pin "4") (pinfunction "I2_4") (pintype "input"))
      (node (ref "E12") (pin "5") (pinfunction "I3_5") (pintype "input"))
      (node (ref "E12") (pin "8") (pinfunction "O_8") (pintype "output"))
    )
    (net (code "38") (name "Net-(E12C-O)") (class "Default")
      (node (ref "E1") (pin "8") (pinfunction "W3_8") (pintype "input"))
      (node (ref "E12") (pin "6") (pinfunction "O_6") (pintype "output"))
      (node (ref "E2") (pin "8") (pinfunction "W3_8") (pintype "input"))
      (node (ref "E3") (pin "8") (pinfunction "W3_8") (pintype "input"))
      (node (ref "R14") (pin "1") (pinfunction "1_1") (pintype "passive"))
    )
    (net (code "39") (name "Net-(E12D-I3)") (class "Default")
      (node (ref "E1") (pin "4") (pinfunction "R3_4") (pintype "input"))
      (node (ref "E12") (pin "13") (pinfunction "I3_13") (pintype "input"))
      (node (ref "E2") (pin "4") (pinfunction "R3_4") (pintype "input"))
      (node (ref "E3") (pin "4") (pinfunction "R3_4") (pintype "input"))
      (node (ref "E7") (pin "6") (pinfunction "O_6") (pintype "output"))
      (node (ref "R6") (pin "1") (pinfunction "1_1") (pintype "passive"))
    )
    (net (code "40") (name "Net-(E13C-I1)") (class "Default")
      (node (ref "E13") (pin "10") (pinfunction "I1_10") (pintype "input"))
      (node (ref "E13") (pin "12") (pinfunction "I2_12") (pintype "input"))
      (node (ref "E13") (pin "2") (pinfunction "I1_2") (pintype "input"))
      (node (ref "E13") (pin "4") (pinfunction "I2_4") (pintype "input"))
      (node (ref "E13") (pin "5") (pinfunction "I3_5") (pintype "input"))
      (node (ref "E13") (pin "9") (pinfunction "I0_9") (pintype "input"))
      (node (ref "E14") (pin "10") (pinfunction "I1_10") (pintype "input"))
      (node (ref "E14") (pin "12") (pinfunction "I2_12") (pintype "input"))
      (node (ref "E14") (pin "2") (pinfunction "I1_2") (pintype "input"))
      (node (ref "E14") (pin "4") (pinfunction "I2_4") (pintype "input"))
      (node (ref "E14") (pin "5") (pinfunction "I3_5") (pintype "input"))
      (node (ref "E14") (pin "9") (pinfunction "I0_9") (pintype "input"))
      (node (ref "R31") (pin "2") (pinfunction "2_2") (pintype "passive"))
    )
    (net (code "41") (name "Net-(E13C-O)") (class "Default")
      (node (ref "E13") (pin "6") (pinfunction "O_6") (pintype "output"))
      (node (ref "E18") (pin "13") (pinfunction "I3_13") (pintype "input"))
      (node (ref "E4") (pin "3") (pinfunction "R2_3") (pintype "input"))
      (node (ref "E5") (pin "3") (pinfunction "R2_3") (pintype "input"))
      (node (ref "E6") (pin "3") (pinfunction "R2_3") (pintype "input"))
      (node (ref "R3") (pin "1") (pinfunction "1_1") (pintype "passive"))
    )
    (net (code "42") (name "Net-(E13D-O)") (class "Default")
      (node (ref "E13") (pin "8") (pinfunction "O_8") (pintype "output"))
      (node (ref "E17") (pin "13") (pinfunction "I3_13") (pintype "input"))
      (node (ref "E4") (pin "4") (pinfunction "R3_4") (pintype "input"))
      (node (ref "E5") (pin "4") (pinfunction "R3_4") (pintype "input"))
      (node (ref "E6") (pin "4") (pinfunction "R3_4") (pintype "input"))
      (node (ref "R2") (pin "1") (pinfunction "1_1") (pintype "passive"))
    )
    (net (code "43") (name "Net-(E14C-O)") (class "Default")
      (node (ref "E14") (pin "6") (pinfunction "O_6") (pintype "output"))
      (node (ref "E16") (pin "13") (pinfunction "I3_13") (pintype "input"))
      (node (ref "E4") (pin "1") (pinfunction "R0_1") (pintype "input"))
      (node (ref "E5") (pin "1") (pinfunction "R0_1") (pintype "input"))
      (node (ref "E6") (pin "1") (pinfunction "R0_1") (pintype "input"))
      (node (ref "R5") (pin "1") (pinfunction "1_1") (pintype "passive"))
    )
    (net (code "44") (name "Net-(E14D-O)") (class "Default")
      (node (ref "E14") (pin "8") (pinfunction "O_8") (pintype "output"))
      (node (ref "E15") (pin "13") (pinfunction "I3_13") (pintype "input"))
      (node (ref "E4") (pin "2") (pinfunction "R1_2") (pintype "input"))
      (node (ref "E5") (pin "2") (pinfunction "R1_2") (pintype "input"))
      (node (ref "E6") (pin "2") (pinfunction "R1_2") (pintype "input"))
      (node (ref "R4") (pin "1") (pinfunction "1_1") (pintype "passive"))
    )
    (net (code "45") (name "Net-(E15C-I0)") (class "Default")
      (node (ref "E15") (pin "1") (pinfunction "I0_1") (pintype "input"))
      (node (ref "E15") (pin "2") (pinfunction "I1_2") (pintype "input"))
      (node (ref "E15") (pin "4") (pinfunction "I2_4") (pintype "input"))
      (node (ref "E15") (pin "5") (pinfunction "I3_5") (pintype "input"))
      (node (ref "E15") (pin "8") (pinfunction "O_8") (pintype "output"))
    )
    (net (code "46") (name "Net-(E15C-O)") (class "Default")
      (node (ref "E15") (pin "6") (pinfunction "O_6") (pintype "output"))
      (node (ref "E4") (pin "10") (pinfunction "W1_10") (pintype "input"))
      (node (ref "E5") (pin "10") (pinfunction "W1_10") (pintype "input"))
      (node (ref "E6") (pin "10") (pinfunction "W1_10") (pintype "input"))
      (node (ref "R12") (pin "1") (pinfunction "1_1") (pintype "passive"))
    )
    (net (code "47") (name "Net-(E15D-I0)") (class "Default")
      (node (ref "E15") (pin "10") (pinfunction "I1_10") (pintype "input"))
      (node (ref "E15") (pin "12") (pinfunction "I2_12") (pintype "input"))
      (node (ref "E15") (pin "9") (pinfunction "I0_9") (pintype "input"))
      (node (ref "E16") (pin "10") (pinfunction "I1_10") (pintype "input"))
      (node (ref "E16") (pin "12") (pinfunction "I2_12") (pintype "input"))
      (node (ref "E16") (pin "9") (pinfunction "I0_9") (pintype "input"))
      (node (ref "E17") (pin "10") (pinfunction "I1_10") (pintype "input"))
      (node (ref "E17") (pin "12") (pinfunction "I2_12") (pintype "input"))
      (node (ref "E17") (pin "9") (pinfunction "I0_9") (pintype "input"))
      (node (ref "E18") (pin "10") (pinfunction "I1_10") (pintype "input"))
      (node (ref "E18") (pin "12") (pinfunction "I2_12") (pintype "input"))
      (node (ref "E18") (pin "9") (pinfunction "I0_9") (pintype "input"))
      (node (ref "E19") (pin "6") (pinfunction "O_6") (pintype "output"))
    )
    (net (code "48") (name "Net-(E16C-I0)") (class "Default")
      (node (ref "E16") (pin "1") (pinfunction "I0_1") (pintype "input"))
      (node (ref "E16") (pin "2") (pinfunction "I1_2") (pintype "input"))
      (node (ref "E16") (pin "4") (pinfunction "I2_4") (pintype "input"))
      (node (ref "E16") (pin "5") (pinfunction "I3_5") (pintype "input"))
      (node (ref "E16") (pin "8") (pinfunction "O_8") (pintype "output"))
    )
    (net (code "49") (name "Net-(E16C-O)") (class "Default")
      (node (ref "E16") (pin "6") (pinfunction "O_6") (pintype "output"))
      (node (ref "E4") (pin "11") (pinfunction "W0_11") (pintype "input"))
      (node (ref "E5") (pin "11") (pinfunction "W0_11") (pintype "input"))
      (node (ref "E6") (pin "11") (pinfunction "W0_11") (pintype "input"))
      (node (ref "R13") (pin "1") (pinfunction "1_1") (pintype "passive"))
    )
    (net (code "50") (name "Net-(E17C-I0)") (class "Default")
      (node (ref "E17") (pin "1") (pinfunction "I0_1") (pintype "input"))
      (node (ref "E17") (pin "2") (pinfunction "I1_2") (pintype "input"))
      (node (ref "E17") (pin "4") (pinfunction "I2_4") (pintype "input"))
      (node (ref "E17") (pin "5") (pinfunction "I3_5") (pintype "input"))
      (node (ref "E17") (pin "8") (pinfunction "O_8") (pintype "output"))
    )
    (net (code "51") (name "Net-(E17C-O)") (class "Default")
      (node (ref "E17") (pin "6") (pinfunction "O_6") (pintype "output"))
      (node (ref "E4") (pin "8") (pinfunction "W3_8") (pintype "input"))
      (node (ref "E5") (pin "8") (pinfunction "W3_8") (pintype "input"))
      (node (ref "E6") (pin "8") (pinfunction "W3_8") (pintype "input"))
      (node (ref "R10") (pin "1") (pinfunction "1_1") (pintype "passive"))
    )
    (net (code "52") (name "Net-(E18C-I0)") (class "Default")
      (node (ref "E18") (pin "1") (pinfunction "I0_1") (pintype "input"))
      (node (ref "E18") (pin "2") (pinfunction "I1_2") (pintype "input"))
      (node (ref "E18") (pin "4") (pinfunction "I2_4") (pintype "input"))
      (node (ref "E18") (pin "5") (pinfunction "I3_5") (pintype "input"))
      (node (ref "E18") (pin "8") (pinfunction "O_8") (pintype "output"))
    )
    (net (code "53") (name "Net-(E18C-O)") (class "Default")
      (node (ref "E18") (pin "6") (pinfunction "O_6") (pintype "output"))
      (node (ref "E4") (pin "9") (pinfunction "W2_9") (pintype "input"))
      (node (ref "E5") (pin "9") (pinfunction "W2_9") (pintype "input"))
      (node (ref "E6") (pin "9") (pinfunction "W2_9") (pintype "input"))
      (node (ref "R11") (pin "1") (pinfunction "1_1") (pintype "passive"))
    )
    (net (code "54") (name "Net-(E19C-I1)") (class "Default")
      (node (ref "D1") (pin "C") (pinfunction "C_C") (pintype "passive"))
      (node (ref "E19") (pin "10") (pinfunction "I1_10") (pintype "input"))
      (node (ref "E19") (pin "12") (pinfunction "I2_12") (pintype "input"))
      (node (ref "E19") (pin "2") (pinfunction "I1_2") (pintype "input"))
      (node (ref "E19") (pin "4") (pinfunction "I2_4") (pintype "input"))
      (node (ref "E19") (pin "5") (pinfunction "I3_5") (pintype "input"))
      (node (ref "E19") (pin "9") (pinfunction "I0_9") (pintype "input"))
      (node (ref "R32") (pin "2") (pinfunction "2_2") (pintype "passive"))
    )
    (net (code "55") (name "VCC") (class "Default")
      (node (ref "B") (pin "V2") (pinfunction "P_V2") (pintype "passive"))
      (node (ref "C10") (pin "1") (pinfunction "1_1") (pintype "passive"))
      (node (ref "C12") (pin "1") (pinfunction "1_1") (pintype "passive"))
      (node (ref "C14") (pin "1") (pinfunction "1_1") (pintype "passive"))
      (node (ref "C16") (pin "1") (pinfunction "1_1") (pintype "passive"))
      (node (ref "C18") (pin "1") (pinfunction "1_1") (pintype "passive"))
      (node (ref "C20") (pin "1") (pinfunction "1_1") (pintype "passive"))
      (node (ref "C22") (pin "1") (pinfunction "1_1") (pintype "passive"))
      (node (ref "C24") (pin "1") (pinfunction "1_1") (pintype "passive"))
      (node (ref "C26") (pin "1") (pinfunction "1_1") (pintype "passive"))
      (node (ref "C28") (pin "1") (pinfunction "1_1") (pintype "passive"))
      (node (ref "C30") (pin "1") (pinfunction "1_1") (pintype "passive"))
      (node (ref "C32") (pin "1") (pinfunction "1_1") (pintype "passive"))
      (node (ref "C34") (pin "1") (pinfunction "1_1") (pintype "passive"))
      (node (ref "C36") (pin "1") (pinfunction "1_1") (pintype "passive"))
      (node (ref "C38") (pin "1") (pinfunction "1_1") (pintype "passive"))
      (node (ref "C4") (pin "+") (pinfunction "+_+") (pintype "passive"))
      (node (ref "C40") (pin "1") (pinfunction "1_1") (pintype "passive"))
      (node (ref "C42") (pin "1") (pinfunction "1_1") (pintype "passive"))
      (node (ref "C6") (pin "1") (pinfunction "1_1") (pintype "passive"))
      (node (ref "C8") (pin "1") (pinfunction "1_1") (pintype "passive"))
      (node (ref "E1") (pin "12") (pinfunction "VCC_12") (pintype "power_in"))
      (node (ref "E10") (pin "14") (pinfunction "VCC_14") (pintype "power_in"))
      (node (ref "E11") (pin "14") (pinfunction "VCC_14") (pintype "power_in"))
      (node (ref "E12") (pin "14") (pinfunction "VCC_14") (pintype "power_in"))
      (node (ref "E13") (pin "14") (pinfunction "VCC_14") (pintype "power_in"))
      (node (ref "E14") (pin "14") (pinfunction "VCC_14") (pintype "power_in"))
      (node (ref "E15") (pin "14") (pinfunction "VCC_14") (pintype "power_in"))
      (node (ref "E16") (pin "14") (pinfunction "VCC_14") (pintype "power_in"))
      (node (ref "E17") (pin "14") (pinfunction "VCC_14") (pintype "power_in"))
      (node (ref "E18") (pin "14") (pinfunction "VCC_14") (pintype "power_in"))
      (node (ref "E19") (pin "14") (pinfunction "VCC_14") (pintype "power_in"))
      (node (ref "E2") (pin "12") (pinfunction "VCC_12") (pintype "power_in"))
      (node (ref "E3") (pin "12") (pinfunction "VCC_12") (pintype "power_in"))
      (node (ref "E4") (pin "12") (pinfunction "VCC_12") (pintype "power_in"))
      (node (ref "E5") (pin "12") (pinfunction "VCC_12") (pintype "power_in"))
      (node (ref "E6") (pin "12") (pinfunction "VCC_12") (pintype "power_in"))
      (node (ref "E7") (pin "14") (pinfunction "VCC_14") (pintype "power_in"))
      (node (ref "E8") (pin "14") (pinfunction "VCC_14") (pintype "power_in"))
      (node (ref "E9") (pin "14") (pinfunction "VCC_14") (pintype "power_in"))
    )
  )
)
